# MTAP-Embedded.net
KiCad netlist of a schematic drawn in EAGLE
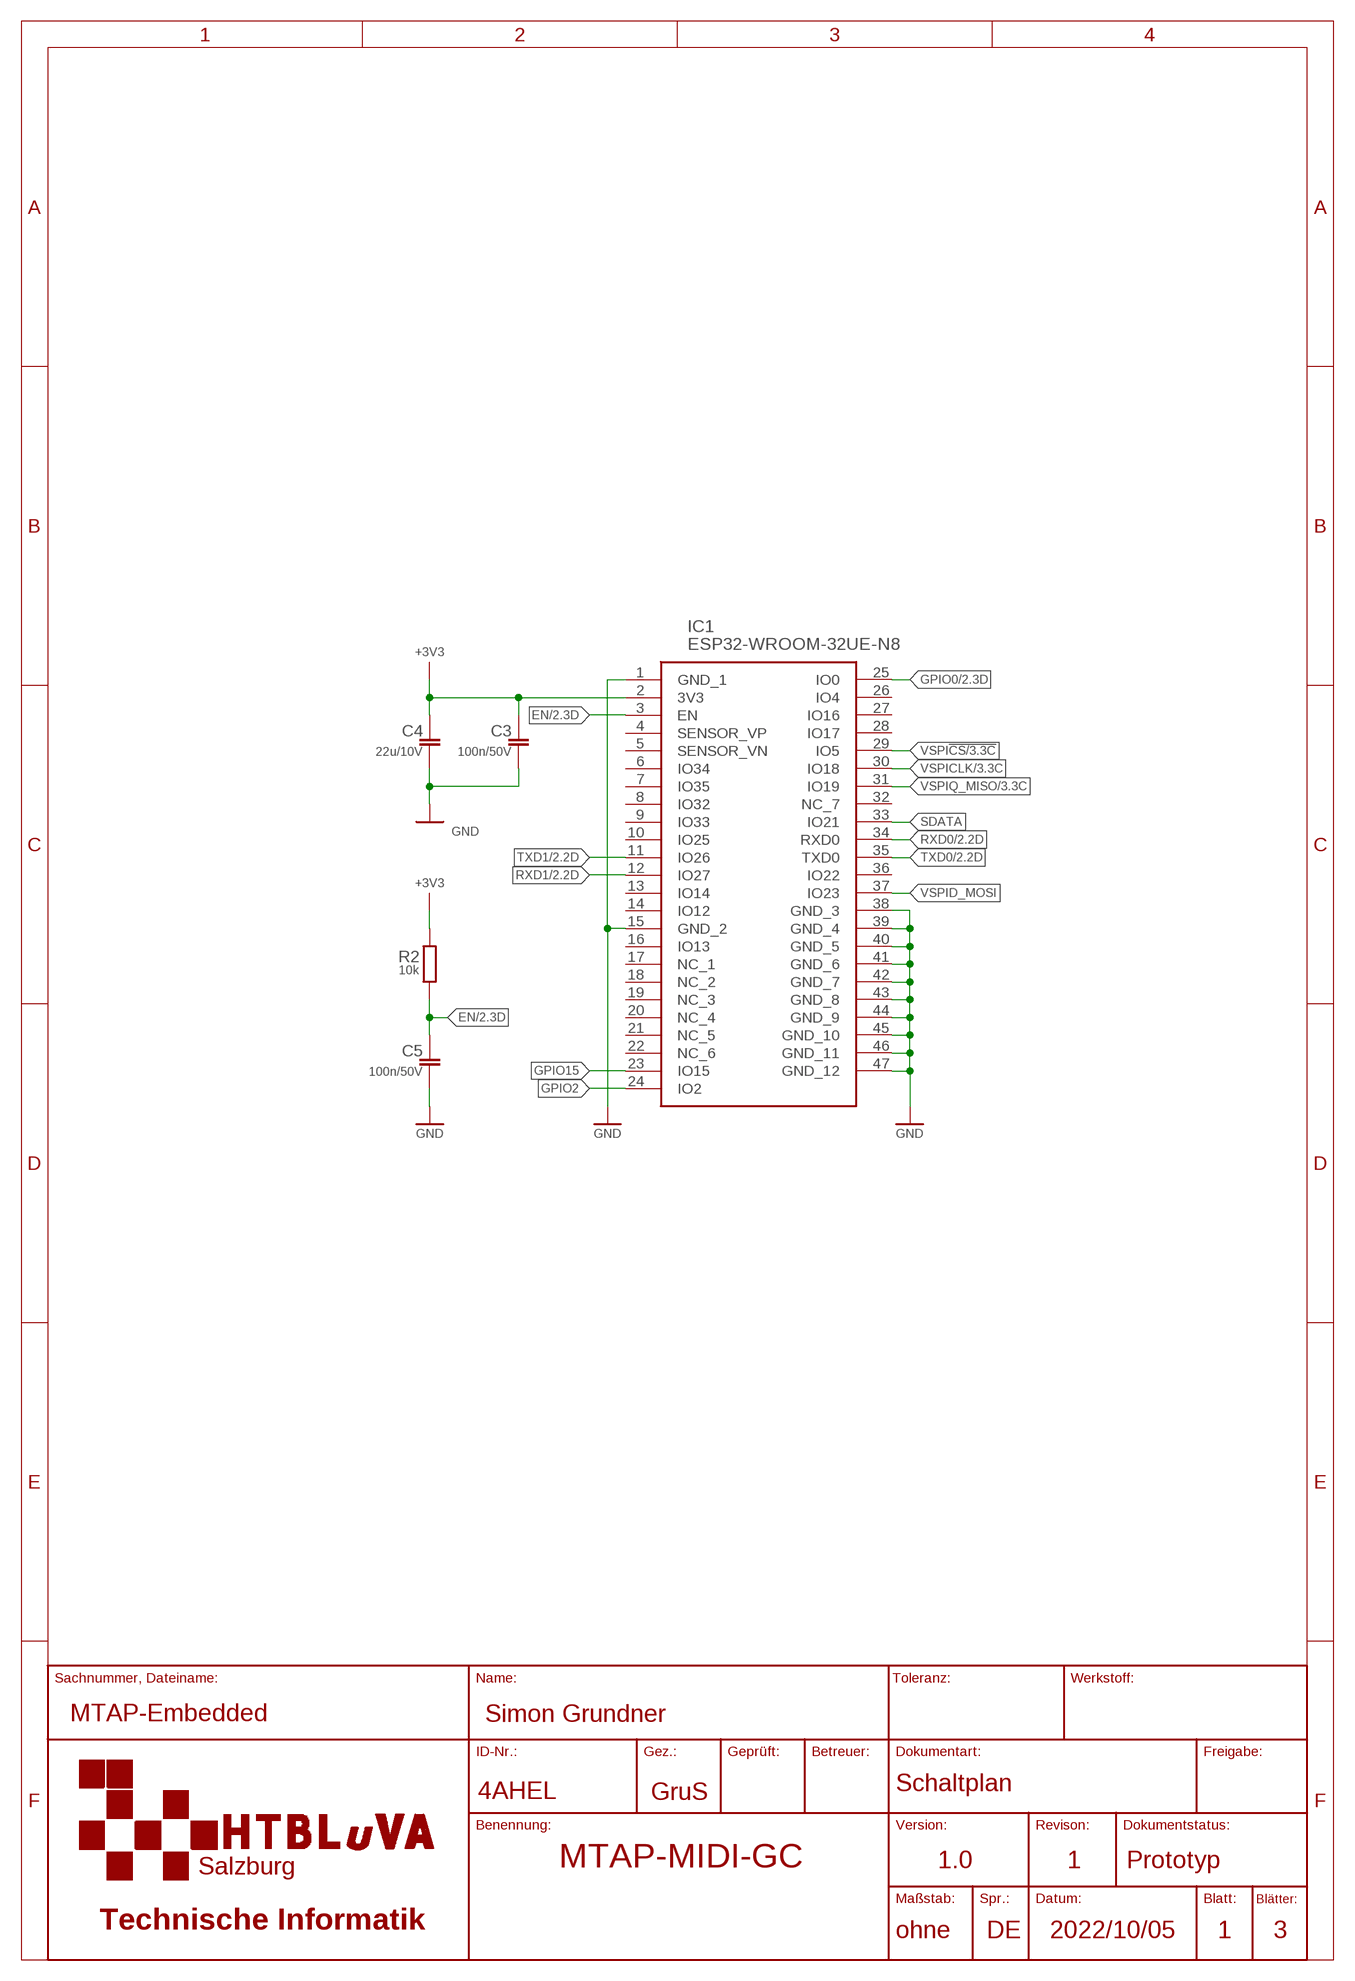
[diagram p0: schematic, sheet 1]
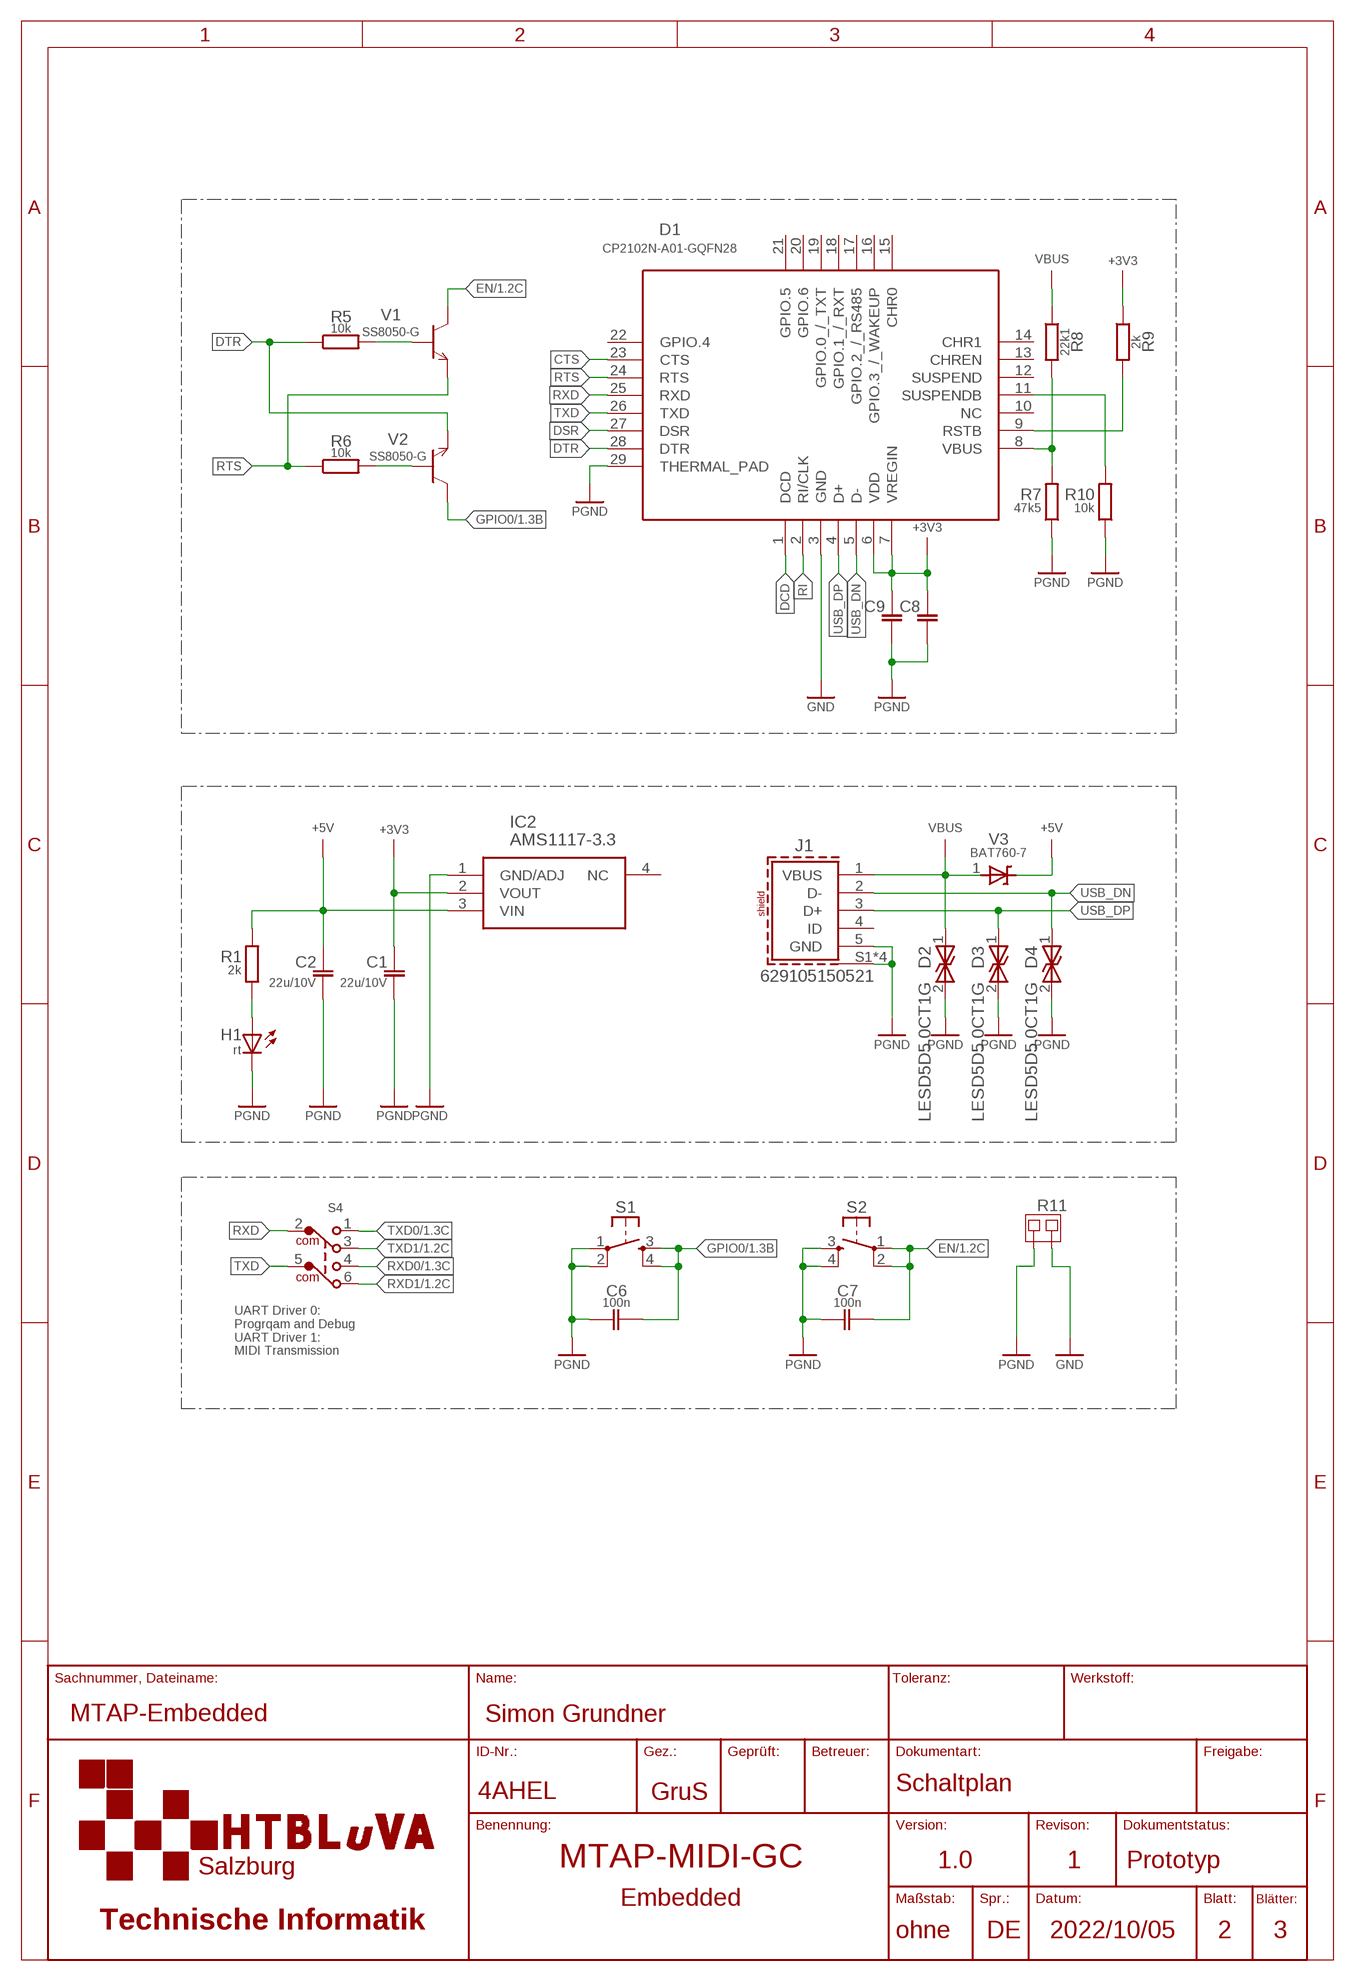
[diagram p1: schematic, sheet 2]
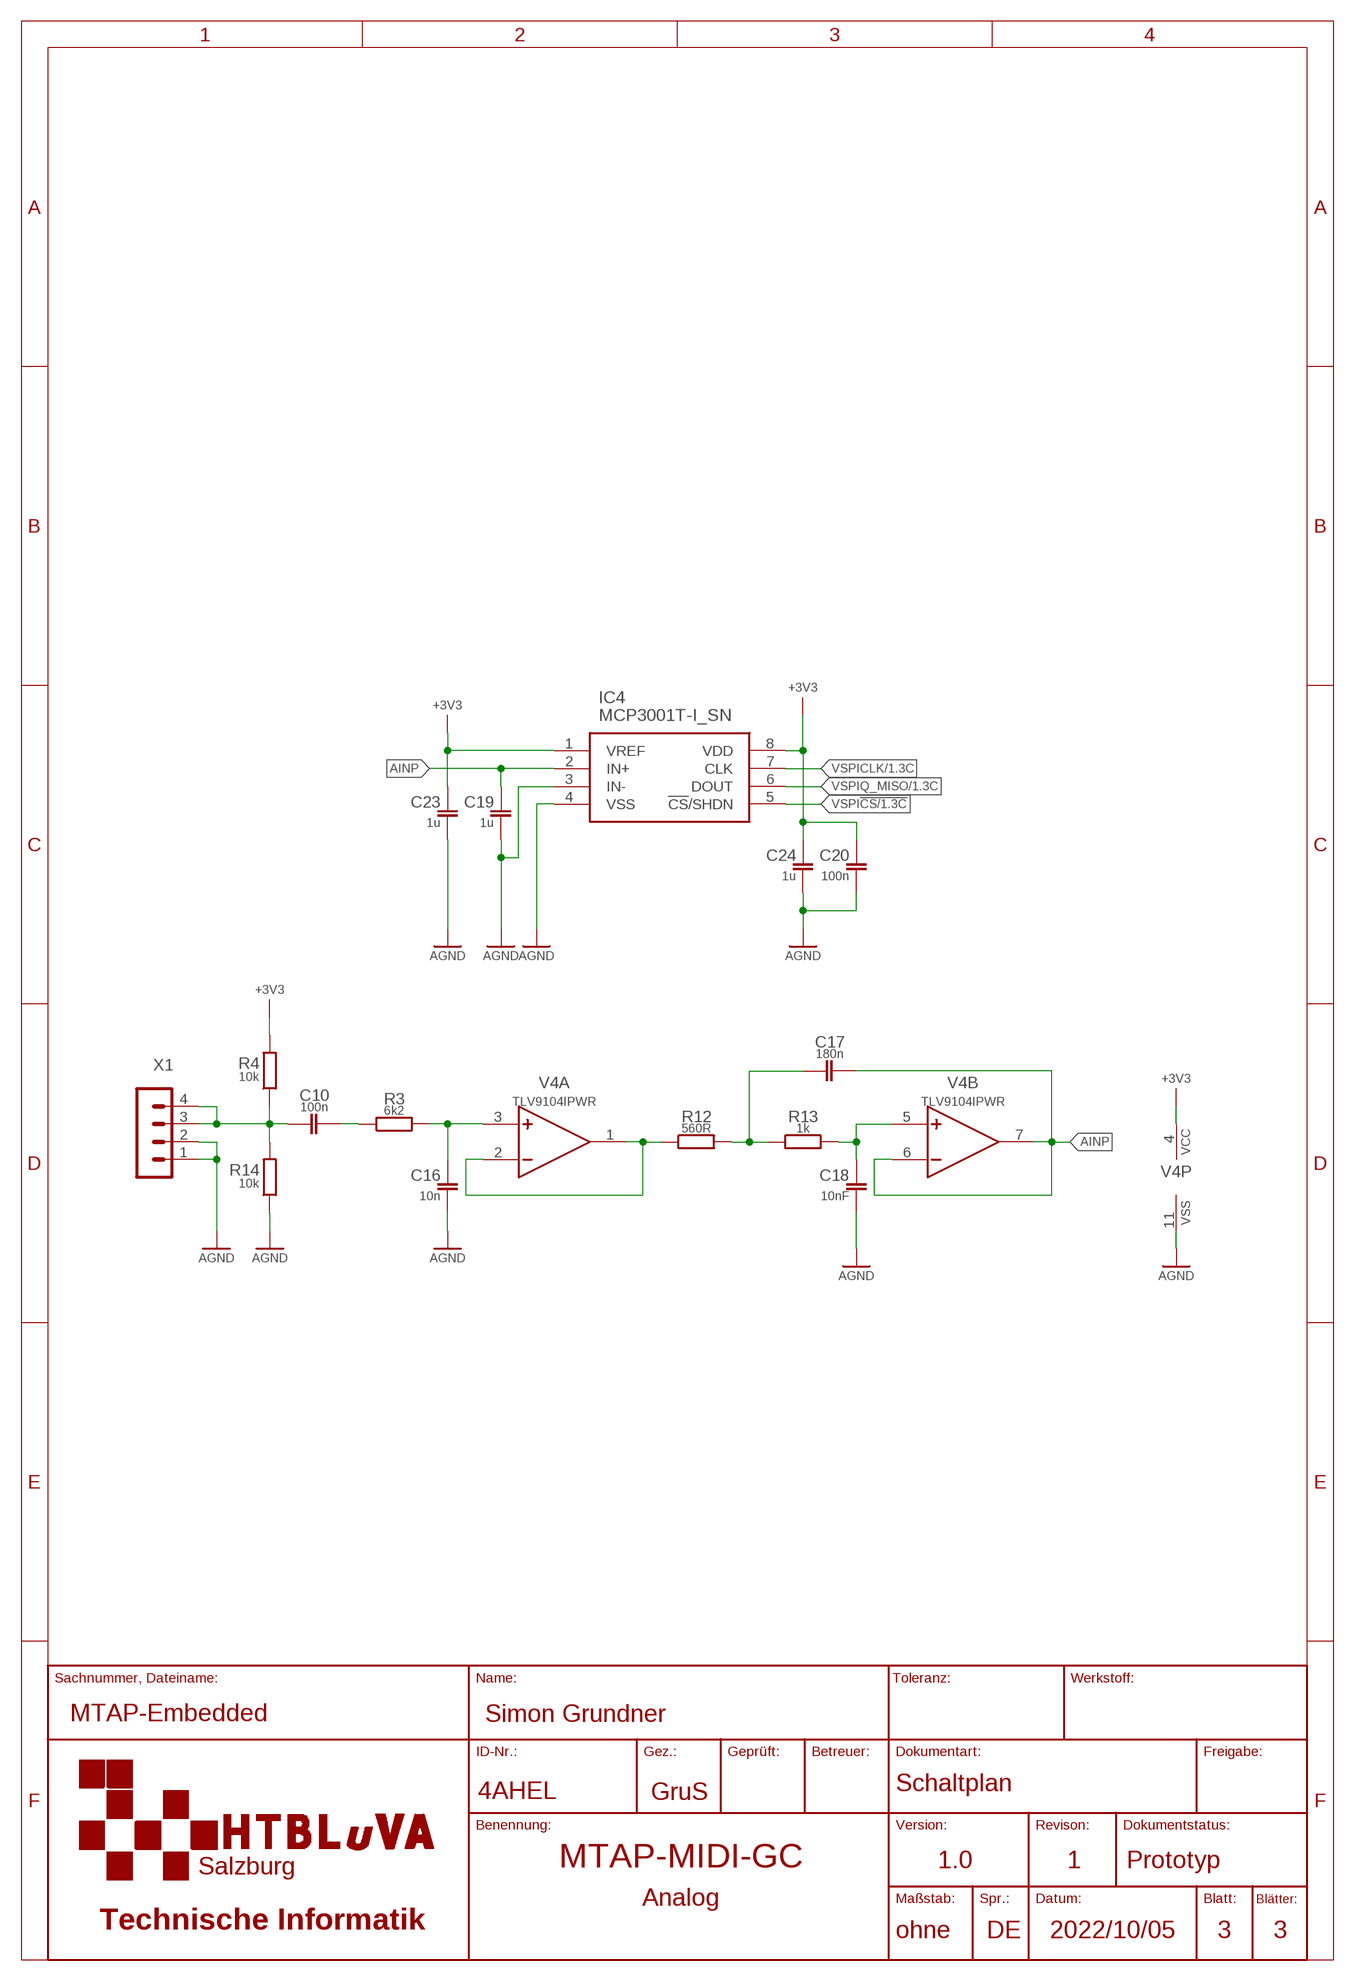
[diagram p2: schematic, sheet 3]

(export (version "E")
  (design (tool "Eeschema 10.0.6"))
  (components
    (comp (ref "C1")
      (value "22u/10V")
      (footprint "eagle-import:C0805")
      (libsource (lib "eagle-import") (part "C-EUC0805"))
    )
    (comp (ref "C2")
      (value "22u/10V")
      (footprint "eagle-import:C0805")
      (libsource (lib "eagle-import") (part "C-EUC0805"))
    )
    (comp (ref "C6")
      (value "100n")
      (footprint "eagle-import:C0805")
      (libsource (lib "eagle-import") (part "C-EULC0805"))
    )
    (comp (ref "C7")
      (value "100n")
      (footprint "eagle-import:C0805")
      (libsource (lib "eagle-import") (part "C-EULC0805"))
    )
    (comp (ref "C8")
      (value "C-EUC0805")
      (footprint "eagle-import:C0805")
      (libsource (lib "eagle-import") (part "C-EUC0805"))
    )
    (comp (ref "C9")
      (value "C-EUC0805")
      (footprint "eagle-import:C0805")
      (libsource (lib "eagle-import") (part "C-EUC0805"))
    )
    (comp (ref "D1")
      (value "CP2102N-A01-GQFN28")
      (footprint "eagle-import:QFN28")
      (fields (field (name "MOUSER_PART_NUMBER") "634-CP2102NA01GQFN28"))
      (libsource (lib "eagle-import") (part "CP2102N-A01-GQFN28"))
    )
    (comp (ref "D2")
      (value "LESD5D5.0CT1G")
      (footprint "eagle-import:SOD523")
      (libsource (lib "eagle-import") (part "LESD5D5.0CT1G"))
    )
    (comp (ref "D3")
      (value "LESD5D5.0CT1G")
      (footprint "eagle-import:SOD523")
      (libsource (lib "eagle-import") (part "LESD5D5.0CT1G"))
    )
    (comp (ref "D4")
      (value "LESD5D5.0CT1G")
      (footprint "eagle-import:SOD523")
      (libsource (lib "eagle-import") (part "LESD5D5.0CT1G"))
    )
    (comp (ref "H1")
      (value "rt")
      (footprint "eagle-import:CHIP-LED0805")
      (libsource (lib "eagle-import") (part "LEDCHIP-LED0805"))
    )
    (comp (ref "IC2")
      (value "AMS1117-3.3")
      (footprint "eagle-import:SOT229P700X180-4N")
      (libsource (lib "eagle-import") (part "AMS1117-3.3"))
    )
    (comp (ref "J1")
      (value "629105150521")
      (footprint "eagle-import:629105150521")
      (libsource (lib "eagle-import") (part "629105150521"))
    )
    (comp (ref "R1")
      (value "2k")
      (footprint "eagle-import:R0805")
      (libsource (lib "eagle-import") (part "R-EUSR0805"))
    )
    (comp (ref "R5")
      (value "10k")
      (footprint "eagle-import:R0805")
      (libsource (lib "eagle-import") (part "R-EU_R0805"))
    )
    (comp (ref "R6")
      (value "10k")
      (footprint "eagle-import:R0805")
      (libsource (lib "eagle-import") (part "R-EU_R0805"))
    )
    (comp (ref "R7")
      (value "47k5")
      (footprint "eagle-import:R0805")
      (libsource (lib "eagle-import") (part "R-EUSR0805"))
    )
    (comp (ref "R8")
      (value "22k1")
      (footprint "eagle-import:R0805")
      (libsource (lib "eagle-import") (part "R-EU_R0805"))
    )
    (comp (ref "R9")
      (value "2k")
      (footprint "eagle-import:R0805")
      (libsource (lib "eagle-import") (part "R-EU_R0805"))
    )
    (comp (ref "R10")
      (value "10k")
      (footprint "eagle-import:R0805")
      (libsource (lib "eagle-import") (part "R-EUSR0805"))
    )
    (comp (ref "R11")
      (value "0R")
      (footprint "eagle-import:MYLIB_SJ-SHORT")
      (libsource (lib "eagle-import") (part "JUMPSMD1FACH-1SHORT"))
    )
    (comp (ref "S1")
      (value "TASTE10XXWE")
      (footprint "eagle-import:WE_436331045822")
      (libsource (lib "eagle-import") (part "TASTE10XXWE"))
    )
    (comp (ref "S2")
      (value "TASTE10XXWE")
      (footprint "eagle-import:WE_436331045822")
      (libsource (lib "eagle-import") (part "TASTE10XXWE"))
    )
    (comp (ref "S4")
      (value "452404020202")
      (footprint "eagle-import:452404020202")
      (libsource (lib "eagle-import") (part "452404020202"))
    )
    (comp (ref "V1")
      (value "SS8050-G")
      (footprint "eagle-import:SOT95P240X115-3N")
      (fields (field (name "MOUSER_PART_NUMBER") "750-SS8050-G"))
      (libsource (lib "eagle-import") (part "SS8050-G"))
    )
    (comp (ref "V2")
      (value "SS8050-G")
      (footprint "eagle-import:SOT95P240X115-3N")
      (fields (field (name "MOUSER_PART_NUMBER") "750-SS8050-G"))
      (libsource (lib "eagle-import") (part "SS8050-G"))
    )
    (comp (ref "V3")
      (value "BAT760-7")
      (footprint "eagle-import:SOD323")
      (fields (field (name "MOUSER_PART_NUMBER") "621-BAT760-7"))
      (libsource (lib "eagle-import") (part "BAT760-7"))
    )
    (comp (ref "C3")
      (value "100n/50V")
      (footprint "eagle-import:C0805")
      (libsource (lib "eagle-import") (part "C-EUC0805"))
    )
    (comp (ref "C4")
      (value "22u/10V")
      (footprint "eagle-import:C0805")
      (libsource (lib "eagle-import") (part "C-EUC0805"))
    )
    (comp (ref "C5")
      (value "100n/50V")
      (footprint "eagle-import:C0805")
      (libsource (lib "eagle-import") (part "C-EUC0805"))
    )
    (comp (ref "IC1")
      (value "ESP32-WROOM-32UE-N8")
      (footprint "eagle-import:ESP32WROOM32UEN8")
      (fields (field (name "MOUSER_PART_NUMBER") "356-ESP32WRM32UE64UH"))
      (libsource (lib "eagle-import") (part "ESP32-WROOM-32UE-N8"))
    )
    (comp (ref "R2")
      (value "10k")
      (footprint "eagle-import:R0805")
      (libsource (lib "eagle-import") (part "R-EUSR0805"))
    )
    (comp (ref "C10")
      (value "100n")
      (footprint "eagle-import:C0805")
      (libsource (lib "eagle-import") (part "C-EULC0805"))
    )
    (comp (ref "C16")
      (value "10n")
      (footprint "eagle-import:C0805")
      (libsource (lib "eagle-import") (part "C-EUC0805"))
    )
    (comp (ref "C17")
      (value "180n")
      (footprint "eagle-import:C0805")
      (libsource (lib "eagle-import") (part "C-EULC0805"))
    )
    (comp (ref "C18")
      (value "10nF")
      (footprint "eagle-import:C0805")
      (libsource (lib "eagle-import") (part "C-EUC0805"))
    )
    (comp (ref "C19")
      (value "1u")
      (footprint "eagle-import:C0805")
      (libsource (lib "eagle-import") (part "C-EUC0805"))
    )
    (comp (ref "C20")
      (value "100n")
      (footprint "eagle-import:C0805")
      (libsource (lib "eagle-import") (part "C-EUC0805"))
    )
    (comp (ref "C23")
      (value "1u")
      (footprint "eagle-import:C0805")
      (libsource (lib "eagle-import") (part "C-EUC0805"))
    )
    (comp (ref "C24")
      (value "1u")
      (footprint "eagle-import:C0805")
      (libsource (lib "eagle-import") (part "C-EUC0805"))
    )
    (comp (ref "IC4")
      (value "MCP3001T-I_SN")
      (footprint "eagle-import:SOIC127P600X175-8N")
      (fields
        (field (name "ARROW_PART_NUMBER") "MCP3001T-I/SN")
        (field (name "MOUSER_PART_NUMBER") "579-MCP3001T-I/SN")
      )
      (libsource (lib "eagle-import") (part "MCP3001T-I_SN"))
    )
    (comp (ref "R3")
      (value "6k2")
      (footprint "eagle-import:R0805")
      (libsource (lib "eagle-import") (part "R-EU_R0805"))
    )
    (comp (ref "R4")
      (value "10k")
      (footprint "eagle-import:R0805")
      (libsource (lib "eagle-import") (part "R-EUSR0805"))
    )
    (comp (ref "R12")
      (value "560R")
      (footprint "eagle-import:R0805")
      (libsource (lib "eagle-import") (part "R-EU_R0805"))
    )
    (comp (ref "R13")
      (value "1k")
      (footprint "eagle-import:R0805")
      (libsource (lib "eagle-import") (part "R-EU_R0805"))
    )
    (comp (ref "R14")
      (value "10k")
      (footprint "eagle-import:R0805")
      (libsource (lib "eagle-import") (part "R-EUSR0805"))
    )
    (comp (ref "V4")
      (value "TLV9104IPWR")
      (footprint "eagle-import:SOP65P640X120-14N")
      (fields (field (name "MOUSER_PART_NUMBER") "595-TLV9104IPWR"))
      (libsource (lib "eagle-import") (part "TLV9104IPWR"))
    )
    (comp (ref "X1")
      (value "MA04-1")
      (footprint "eagle-import:MA04-1")
      (libsource (lib "eagle-import") (part "MA04-1"))
    )
  )
  (nets
    (net (code "1") (name "+3V3") (class "Default")
      (node (ref "C1") (pin "1") (pinfunction "1_1") (pintype "passive"))
      (node (ref "C20") (pin "1") (pinfunction "1_1") (pintype "passive"))
      (node (ref "C23") (pin "1") (pinfunction "1_1") (pintype "passive"))
      (node (ref "C24") (pin "1") (pinfunction "1_1") (pintype "passive"))
      (node (ref "C3") (pin "1") (pinfunction "1_1") (pintype "passive"))
      (node (ref "C4") (pin "1") (pinfunction "1_1") (pintype "passive"))
      (node (ref "C8") (pin "1") (pinfunction "1_1") (pintype "passive"))
      (node (ref "C9") (pin "1") (pinfunction "1_1") (pintype "passive"))
      (node (ref "D1") (pin "6") (pinfunction "VDD_6") (pintype "bidirectional"))
      (node (ref "D1") (pin "7") (pinfunction "VREGIN_7") (pintype "bidirectional"))
      (node (ref "IC1") (pin "2") (pinfunction "3V3_2") (pintype "bidirectional"))
      (node (ref "IC2") (pin "2") (pinfunction "VOUT_2") (pintype "bidirectional"))
      (node (ref "IC4") (pin "1") (pinfunction "VREF_1") (pintype "bidirectional"))
      (node (ref "IC4") (pin "8") (pinfunction "VDD_8") (pintype "bidirectional"))
      (node (ref "R2") (pin "2") (pinfunction "2_2") (pintype "passive"))
      (node (ref "R4") (pin "2") (pinfunction "2_2") (pintype "passive"))
      (node (ref "R9") (pin "1") (pinfunction "1_1") (pintype "passive"))
      (node (ref "V4") (pin "4") (pinfunction "VCC_4") (pintype "power_in"))
    )
    (net (code "2") (name "+5V") (class "Default")
      (node (ref "C2") (pin "1") (pinfunction "1_1") (pintype "passive"))
      (node (ref "IC2") (pin "3") (pinfunction "VIN_3") (pintype "bidirectional"))
      (node (ref "R1") (pin "2") (pinfunction "2_2") (pintype "passive"))
      (node (ref "V3") (pin "2") (pinfunction "A_2") (pintype "output"))
    )
    (net (code "3") (name "AGND") (class "Default")
      (node (ref "C16") (pin "2") (pinfunction "2_2") (pintype "passive"))
      (node (ref "C18") (pin "2") (pinfunction "2_2") (pintype "passive"))
      (node (ref "C19") (pin "2") (pinfunction "2_2") (pintype "passive"))
      (node (ref "C20") (pin "2") (pinfunction "2_2") (pintype "passive"))
      (node (ref "C23") (pin "2") (pinfunction "2_2") (pintype "passive"))
      (node (ref "C24") (pin "2") (pinfunction "2_2") (pintype "passive"))
      (node (ref "IC4") (pin "3") (pinfunction "IN-_3") (pintype "bidirectional"))
      (node (ref "IC4") (pin "4") (pinfunction "VSS_4") (pintype "bidirectional"))
      (node (ref "R14") (pin "1") (pinfunction "1_1") (pintype "passive"))
      (node (ref "V4") (pin "11") (pinfunction "VSS_11") (pintype "power_in"))
      (node (ref "X1") (pin "1") (pinfunction "1_1") (pintype "passive"))
      (node (ref "X1") (pin "2") (pinfunction "2_2") (pintype "passive"))
    )
    (net (code "4") (name "AINP") (class "Default")
      (node (ref "C17") (pin "1") (pinfunction "1_1") (pintype "passive"))
      (node (ref "C19") (pin "1") (pinfunction "1_1") (pintype "passive"))
      (node (ref "IC4") (pin "2") (pinfunction "IN+_2") (pintype "bidirectional"))
      (node (ref "V4") (pin "6") (pinfunction "N_6") (pintype "bidirectional"))
      (node (ref "V4") (pin "7") (pinfunction "O_7") (pintype "bidirectional"))
    )
    (net (code "5") (name "CTS") (class "Default")
      (node (ref "D1") (pin "23") (pinfunction "CTS_23") (pintype "bidirectional"))
    )
    (net (code "6") (name "DCD") (class "Default")
      (node (ref "D1") (pin "1") (pinfunction "DCD_1") (pintype "bidirectional"))
    )
    (net (code "7") (name "DSR") (class "Default")
      (node (ref "D1") (pin "27") (pinfunction "DSR_27") (pintype "bidirectional"))
    )
    (net (code "8") (name "DTR") (class "Default")
      (node (ref "D1") (pin "28") (pinfunction "DTR_28") (pintype "bidirectional"))
      (node (ref "R5") (pin "1") (pinfunction "1_1") (pintype "passive"))
      (node (ref "V2") (pin "2") (pinfunction "E_2") (pintype "passive"))
    )
    (net (code "9") (name "EN") (class "Default")
      (node (ref "C5") (pin "1") (pinfunction "1_1") (pintype "passive"))
      (node (ref "C7") (pin "1") (pinfunction "1_1") (pintype "passive"))
      (node (ref "IC1") (pin "3") (pinfunction "EN_3") (pintype "bidirectional"))
      (node (ref "R2") (pin "1") (pinfunction "1_1") (pintype "passive"))
      (node (ref "S2") (pin "1") (pinfunction "P_1") (pintype "passive"))
      (node (ref "S2") (pin "2") (pinfunction "P1_2") (pintype "passive"))
      (node (ref "V1") (pin "3") (pinfunction "C_3") (pintype "passive"))
    )
    (net (code "10") (name "GND") (class "Default")
      (node (ref "C3") (pin "2") (pinfunction "2_2") (pintype "passive"))
      (node (ref "C4") (pin "2") (pinfunction "2_2") (pintype "passive"))
      (node (ref "C5") (pin "2") (pinfunction "2_2") (pintype "passive"))
      (node (ref "D1") (pin "3") (pinfunction "GND_3") (pintype "bidirectional"))
      (node (ref "IC1") (pin "1") (pinfunction "GND_1_1") (pintype "bidirectional"))
      (node (ref "IC1") (pin "15") (pinfunction "GND_2_15") (pintype "bidirectional"))
      (node (ref "IC1") (pin "38") (pinfunction "GND_3_38") (pintype "bidirectional"))
      (node (ref "IC1") (pin "39") (pinfunction "GND_4_39") (pintype "bidirectional"))
      (node (ref "IC1") (pin "40") (pinfunction "GND_5_40") (pintype "bidirectional"))
      (node (ref "IC1") (pin "41") (pinfunction "GND_6_41") (pintype "bidirectional"))
      (node (ref "IC1") (pin "42") (pinfunction "GND_7_42") (pintype "bidirectional"))
      (node (ref "IC1") (pin "43") (pinfunction "GND_8_43") (pintype "bidirectional"))
      (node (ref "IC1") (pin "44") (pinfunction "GND_9_44") (pintype "bidirectional"))
      (node (ref "IC1") (pin "45") (pinfunction "GND_10_45") (pintype "bidirectional"))
      (node (ref "IC1") (pin "46") (pinfunction "GND_11_46") (pintype "bidirectional"))
      (node (ref "IC1") (pin "47") (pinfunction "GND_12_47") (pintype "bidirectional"))
      (node (ref "R11") (pin "2") (pinfunction "2_2") (pintype "passive"))
    )
    (net (code "11") (name "GPIO0") (class "Default")
      (node (ref "C6") (pin "1") (pinfunction "1_1") (pintype "passive"))
      (node (ref "IC1") (pin "25") (pinfunction "IO0_25") (pintype "bidirectional"))
      (node (ref "S1") (pin "3") (pinfunction "S_3") (pintype "passive"))
      (node (ref "S1") (pin "4") (pinfunction "S1_4") (pintype "passive"))
      (node (ref "V2") (pin "3") (pinfunction "C_3") (pintype "passive"))
    )
    (net (code "12") (name "GPIO2") (class "Default")
      (node (ref "IC1") (pin "24") (pinfunction "IO2_24") (pintype "bidirectional"))
    )
    (net (code "13") (name "GPIO15") (class "Default")
      (node (ref "IC1") (pin "23") (pinfunction "IO15_23") (pintype "bidirectional"))
    )
    (net (code "14") (name "Net-(C10-Pad1)") (class "Default")
      (node (ref "C10") (pin "1") (pinfunction "1_1") (pintype "passive"))
      (node (ref "R3") (pin "1") (pinfunction "1_1") (pintype "passive"))
    )
    (net (code "15") (name "Net-(C10-Pad2)") (class "Default")
      (node (ref "C10") (pin "2") (pinfunction "2_2") (pintype "passive"))
      (node (ref "R14") (pin "2") (pinfunction "2_2") (pintype "passive"))
      (node (ref "R4") (pin "1") (pinfunction "1_1") (pintype "passive"))
      (node (ref "X1") (pin "3") (pinfunction "3_3") (pintype "passive"))
      (node (ref "X1") (pin "4") (pinfunction "4_4") (pintype "passive"))
    )
    (net (code "16") (name "Net-(C17-Pad2)") (class "Default")
      (node (ref "C17") (pin "2") (pinfunction "2_2") (pintype "passive"))
      (node (ref "R12") (pin "2") (pinfunction "2_2") (pintype "passive"))
      (node (ref "R13") (pin "1") (pinfunction "1_1") (pintype "passive"))
    )
    (net (code "17") (name "Net-(D1-RSTB)") (class "Default")
      (node (ref "D1") (pin "9") (pinfunction "RSTB_9") (pintype "bidirectional"))
      (node (ref "R9") (pin "2") (pinfunction "2_2") (pintype "passive"))
    )
    (net (code "18") (name "Net-(D1-SUSPENDB)") (class "Default")
      (node (ref "D1") (pin "11") (pinfunction "SUSPENDB_11") (pintype "bidirectional"))
      (node (ref "R10") (pin "2") (pinfunction "2_2") (pintype "passive"))
    )
    (net (code "19") (name "Net-(D1-VBUS)") (class "Default")
      (node (ref "D1") (pin "8") (pinfunction "VBUS_8") (pintype "bidirectional"))
      (node (ref "R7") (pin "2") (pinfunction "2_2") (pintype "passive"))
      (node (ref "R8") (pin "2") (pinfunction "2_2") (pintype "passive"))
    )
    (net (code "20") (name "Net-(H1-PadA)") (class "Default")
      (node (ref "H1") (pin "A") (pinfunction "A_A") (pintype "passive"))
      (node (ref "R1") (pin "1") (pinfunction "1_1") (pintype "passive"))
    )
    (net (code "21") (name "Net-(V1-B)") (class "Default")
      (node (ref "R5") (pin "2") (pinfunction "2_2") (pintype "passive"))
      (node (ref "V1") (pin "1") (pinfunction "B_1") (pintype "passive"))
    )
    (net (code "22") (name "Net-(V2-B)") (class "Default")
      (node (ref "R6") (pin "2") (pinfunction "2_2") (pintype "passive"))
      (node (ref "V2") (pin "1") (pinfunction "B_1") (pintype "passive"))
    )
    (net (code "23") (name "Net-(V4A-N)") (class "Default")
      (node (ref "R12") (pin "1") (pinfunction "1_1") (pintype "passive"))
      (node (ref "V4") (pin "1") (pinfunction "O_1") (pintype "bidirectional"))
      (node (ref "V4") (pin "2") (pinfunction "N_2") (pintype "bidirectional"))
    )
    (net (code "24") (name "Net-(V4A-P)") (class "Default")
      (node (ref "C16") (pin "1") (pinfunction "1_1") (pintype "passive"))
      (node (ref "R3") (pin "2") (pinfunction "2_2") (pintype "passive"))
      (node (ref "V4") (pin "3") (pinfunction "P_3") (pintype "bidirectional"))
    )
    (net (code "25") (name "Net-(V4B-P)") (class "Default")
      (node (ref "C18") (pin "1") (pinfunction "1_1") (pintype "passive"))
      (node (ref "R13") (pin "2") (pinfunction "2_2") (pintype "passive"))
      (node (ref "V4") (pin "5") (pinfunction "P_5") (pintype "bidirectional"))
    )
    (net (code "26") (name "PGND") (class "Default")
      (node (ref "C1") (pin "2") (pinfunction "2_2") (pintype "passive"))
      (node (ref "C2") (pin "2") (pinfunction "2_2") (pintype "passive"))
      (node (ref "C6") (pin "2") (pinfunction "2_2") (pintype "passive"))
      (node (ref "C7") (pin "2") (pinfunction "2_2") (pintype "passive"))
      (node (ref "C8") (pin "2") (pinfunction "2_2") (pintype "passive"))
      (node (ref "C9") (pin "2") (pinfunction "2_2") (pintype "passive"))
      (node (ref "D1") (pin "29") (pinfunction "THERMAL_PAD_29") (pintype "bidirectional"))
      (node (ref "D2") (pin "2") (pinfunction "2_2") (pintype "bidirectional"))
      (node (ref "D3") (pin "2") (pinfunction "2_2") (pintype "bidirectional"))
      (node (ref "D4") (pin "2") (pinfunction "2_2") (pintype "bidirectional"))
      (node (ref "H1") (pin "C") (pinfunction "C_C") (pintype "passive"))
      (node (ref "IC2") (pin "1") (pinfunction "GND/ADJ_1") (pintype "bidirectional"))
      (node (ref "J1") (pin "5") (pinfunction "GND_5") (pintype "passive"))
      (node (ref "J1") (pin "S1") (pinfunction "SHIELD_S1") (pintype "passive"))
      (node (ref "J1") (pin "S2") (pinfunction "SHIELD_S2") (pintype "passive"))
      (node (ref "J1") (pin "S3") (pinfunction "SHIELD_S3") (pintype "passive"))
      (node (ref "J1") (pin "S4") (pinfunction "SHIELD_S4") (pintype "passive"))
      (node (ref "R10") (pin "1") (pinfunction "1_1") (pintype "passive"))
      (node (ref "R11") (pin "1") (pinfunction "1_1") (pintype "passive"))
      (node (ref "R7") (pin "1") (pinfunction "1_1") (pintype "passive"))
      (node (ref "S1") (pin "1") (pinfunction "P_1") (pintype "passive"))
      (node (ref "S1") (pin "2") (pinfunction "P1_2") (pintype "passive"))
      (node (ref "S2") (pin "3") (pinfunction "S_3") (pintype "passive"))
      (node (ref "S2") (pin "4") (pinfunction "S1_4") (pintype "passive"))
    )
    (net (code "27") (name "RI") (class "Default")
      (node (ref "D1") (pin "2") (pinfunction "RI/CLK_2") (pintype "bidirectional"))
    )
    (net (code "28") (name "RTS") (class "Default")
      (node (ref "D1") (pin "24") (pinfunction "RTS_24") (pintype "bidirectional"))
      (node (ref "R6") (pin "1") (pinfunction "1_1") (pintype "passive"))
      (node (ref "V1") (pin "2") (pinfunction "E_2") (pintype "passive"))
    )
    (net (code "29") (name "RXD") (class "Default")
      (node (ref "D1") (pin "25") (pinfunction "RXD_25") (pintype "bidirectional"))
      (node (ref "S4") (pin "2") (pinfunction "COM_2") (pintype "passive"))
    )
    (net (code "30") (name "RXD0") (class "Default")
      (node (ref "IC1") (pin "34") (pinfunction "RXD0_34") (pintype "bidirectional"))
      (node (ref "S4") (pin "4") (pinfunction "4_4") (pintype "passive"))
    )
    (net (code "31") (name "RXD1") (class "Default")
      (node (ref "IC1") (pin "12") (pinfunction "IO27_12") (pintype "bidirectional"))
      (node (ref "S4") (pin "6") (pinfunction "6_6") (pintype "passive"))
    )
    (net (code "32") (name "SDATA") (class "Default")
      (node (ref "IC1") (pin "33") (pinfunction "IO21_33") (pintype "bidirectional"))
    )
    (net (code "33") (name "TXD") (class "Default")
      (node (ref "D1") (pin "26") (pinfunction "TXD_26") (pintype "bidirectional"))
      (node (ref "S4") (pin "5") (pinfunction "COM1_5") (pintype "passive"))
    )
    (net (code "34") (name "TXD0") (class "Default")
      (node (ref "IC1") (pin "35") (pinfunction "TXD0_35") (pintype "bidirectional"))
      (node (ref "S4") (pin "1") (pinfunction "1_1") (pintype "passive"))
    )
    (net (code "35") (name "TXD1") (class "Default")
      (node (ref "IC1") (pin "11") (pinfunction "IO26_11") (pintype "bidirectional"))
      (node (ref "S4") (pin "3") (pinfunction "3_3") (pintype "passive"))
    )
    (net (code "36") (name "USB_DN") (class "Default")
      (node (ref "D1") (pin "5") (pinfunction "D-_5") (pintype "bidirectional"))
      (node (ref "D4") (pin "1") (pinfunction "1_1") (pintype "bidirectional"))
      (node (ref "J1") (pin "2") (pinfunction "D-_2") (pintype "passive"))
    )
    (net (code "37") (name "USB_DP") (class "Default")
      (node (ref "D1") (pin "4") (pinfunction "D+_4") (pintype "bidirectional"))
      (node (ref "D3") (pin "1") (pinfunction "1_1") (pintype "bidirectional"))
      (node (ref "J1") (pin "3") (pinfunction "D+_3") (pintype "passive"))
    )
    (net (code "38") (name "VBUS") (class "Default")
      (node (ref "D2") (pin "1") (pinfunction "1_1") (pintype "bidirectional"))
      (node (ref "J1") (pin "1") (pinfunction "VBUS_1") (pintype "passive"))
      (node (ref "R8") (pin "1") (pinfunction "1_1") (pintype "passive"))
      (node (ref "V3") (pin "1") (pinfunction "K_1") (pintype "input"))
    )
    (net (code "39") (name "VSPICLK") (class "Default")
      (node (ref "IC1") (pin "30") (pinfunction "IO18_30") (pintype "bidirectional"))
      (node (ref "IC4") (pin "7") (pinfunction "CLK_7") (pintype "bidirectional"))
    )
    (net (code "40") (name "VSPID_MOSI") (class "Default")
      (node (ref "IC1") (pin "37") (pinfunction "IO23_37") (pintype "bidirectional"))
    )
    (net (code "41") (name "VSPIQ_MISO") (class "Default")
      (node (ref "IC1") (pin "31") (pinfunction "IO19_31") (pintype "bidirectional"))
      (node (ref "IC4") (pin "6") (pinfunction "DOUT_6") (pintype "bidirectional"))
    )
    (net (code "42") (name "VSPI~{CS}") (class "Default")
      (node (ref "IC1") (pin "29") (pinfunction "IO5_29") (pintype "bidirectional"))
      (node (ref "IC4") (pin "5") (pinfunction "~{CS}/SHDN_5") (pintype "bidirectional"))
    )
    (net (code "43") (name "unconnected-(D1-CHR0-Pad15)") (class "Default")
      (node (ref "D1") (pin "15") (pinfunction "CHR0_15") (pintype "bidirectional"))
    )
    (net (code "44") (name "unconnected-(D1-CHR1-Pad14)") (class "Default")
      (node (ref "D1") (pin "14") (pinfunction "CHR1_14") (pintype "bidirectional"))
    )
    (net (code "45") (name "unconnected-(D1-CHREN-Pad13)") (class "Default")
      (node (ref "D1") (pin "13") (pinfunction "CHREN_13") (pintype "bidirectional"))
    )
    (net (code "46") (name "unconnected-(D1-GPIO.0_{slash}_TXT-Pad19)") (class "Default")
      (node (ref "D1") (pin "19") (pinfunction "GPIO.0_/_TXT_19") (pintype "bidirectional"))
    )
    (net (code "47") (name "unconnected-(D1-GPIO.1_{slash}_RXT-Pad18)") (class "Default")
      (node (ref "D1") (pin "18") (pinfunction "GPIO.1_/_RXT_18") (pintype "bidirectional"))
    )
    (net (code "48") (name "unconnected-(D1-GPIO.2_{slash}_RS485-Pad17)") (class "Default")
      (node (ref "D1") (pin "17") (pinfunction "GPIO.2_/_RS485_17") (pintype "bidirectional"))
    )
    (net (code "49") (name "unconnected-(D1-GPIO.3_{slash}_WAKEUP-Pad16)") (class "Default")
      (node (ref "D1") (pin "16") (pinfunction "GPIO.3_/_WAKEUP_16") (pintype "bidirectional"))
    )
    (net (code "50") (name "unconnected-(D1-GPIO.4-Pad22)") (class "Default")
      (node (ref "D1") (pin "22") (pinfunction "GPIO.4_22") (pintype "bidirectional"))
    )
    (net (code "51") (name "unconnected-(D1-GPIO.5-Pad21)") (class "Default")
      (node (ref "D1") (pin "21") (pinfunction "GPIO.5_21") (pintype "bidirectional"))
    )
    (net (code "52") (name "unconnected-(D1-GPIO.6-Pad20)") (class "Default")
      (node (ref "D1") (pin "20") (pinfunction "GPIO.6_20") (pintype "bidirectional"))
    )
    (net (code "53") (name "unconnected-(D1-NC-Pad10)") (class "Default")
      (node (ref "D1") (pin "10") (pinfunction "NC_10") (pintype "no_connect"))
    )
    (net (code "54") (name "unconnected-(D1-SUSPEND-Pad12)") (class "Default")
      (node (ref "D1") (pin "12") (pinfunction "SUSPEND_12") (pintype "bidirectional"))
    )
    (net (code "55") (name "unconnected-(IC1-IO4-Pad26)") (class "Default")
      (node (ref "IC1") (pin "26") (pinfunction "IO4_26") (pintype "bidirectional"))
    )
    (net (code "56") (name "unconnected-(IC1-IO12-Pad14)") (class "Default")
      (node (ref "IC1") (pin "14") (pinfunction "IO12_14") (pintype "bidirectional"))
    )
    (net (code "57") (name "unconnected-(IC1-IO13-Pad16)") (class "Default")
      (node (ref "IC1") (pin "16") (pinfunction "IO13_16") (pintype "bidirectional"))
    )
    (net (code "58") (name "unconnected-(IC1-IO14-Pad13)") (class "Default")
      (node (ref "IC1") (pin "13") (pinfunction "IO14_13") (pintype "bidirectional"))
    )
    (net (code "59") (name "unconnected-(IC1-IO16-Pad27)") (class "Default")
      (node (ref "IC1") (pin "27") (pinfunction "IO16_27") (pintype "bidirectional"))
    )
    (net (code "60") (name "unconnected-(IC1-IO17-Pad28)") (class "Default")
      (node (ref "IC1") (pin "28") (pinfunction "IO17_28") (pintype "bidirectional"))
    )
    (net (code "61") (name "unconnected-(IC1-IO22-Pad36)") (class "Default")
      (node (ref "IC1") (pin "36") (pinfunction "IO22_36") (pintype "bidirectional"))
    )
    (net (code "62") (name "unconnected-(IC1-IO25-Pad10)") (class "Default")
      (node (ref "IC1") (pin "10") (pinfunction "IO25_10") (pintype "bidirectional"))
    )
    (net (code "63") (name "unconnected-(IC1-IO32-Pad8)") (class "Default")
      (node (ref "IC1") (pin "8") (pinfunction "IO32_8") (pintype "bidirectional"))
    )
    (net (code "64") (name "unconnected-(IC1-IO33-Pad9)") (class "Default")
      (node (ref "IC1") (pin "9") (pinfunction "IO33_9") (pintype "bidirectional"))
    )
    (net (code "65") (name "unconnected-(IC1-IO34-Pad6)") (class "Default")
      (node (ref "IC1") (pin "6") (pinfunction "IO34_6") (pintype "bidirectional"))
    )
    (net (code "66") (name "unconnected-(IC1-IO35-Pad7)") (class "Default")
      (node (ref "IC1") (pin "7") (pinfunction "IO35_7") (pintype "bidirectional"))
    )
    (net (code "67") (name "unconnected-(IC1-NC_1-Pad17)") (class "Default")
      (node (ref "IC1") (pin "17") (pinfunction "NC_1_17") (pintype "bidirectional"))
    )
    (net (code "68") (name "unconnected-(IC1-NC_2-Pad18)") (class "Default")
      (node (ref "IC1") (pin "18") (pinfunction "NC_2_18") (pintype "bidirectional"))
    )
    (net (code "69") (name "unconnected-(IC1-NC_3-Pad19)") (class "Default")
      (node (ref "IC1") (pin "19") (pinfunction "NC_3_19") (pintype "bidirectional"))
    )
    (net (code "70") (name "unconnected-(IC1-NC_4-Pad20)") (class "Default")
      (node (ref "IC1") (pin "20") (pinfunction "NC_4_20") (pintype "bidirectional"))
    )
    (net (code "71") (name "unconnected-(IC1-NC_5-Pad21)") (class "Default")
      (node (ref "IC1") (pin "21") (pinfunction "NC_5_21") (pintype "bidirectional"))
    )
    (net (code "72") (name "unconnected-(IC1-NC_6-Pad22)") (class "Default")
      (node (ref "IC1") (pin "22") (pinfunction "NC_6_22") (pintype "bidirectional"))
    )
    (net (code "73") (name "unconnected-(IC1-NC_7-Pad32)") (class "Default")
      (node (ref "IC1") (pin "32") (pinfunction "NC_7_32") (pintype "bidirectional"))
    )
    (net (code "74") (name "unconnected-(IC1-SENSOR_VN-Pad5)") (class "Default")
      (node (ref "IC1") (pin "5") (pinfunction "SENSOR_VN_5") (pintype "bidirectional"))
    )
    (net (code "75") (name "unconnected-(IC1-SENSOR_VP-Pad4)") (class "Default")
      (node (ref "IC1") (pin "4") (pinfunction "SENSOR_VP_4") (pintype "bidirectional"))
    )
    (net (code "76") (name "unconnected-(IC2-NC-Pad4)") (class "Default")
      (node (ref "IC2") (pin "4") (pinfunction "NC_4") (pintype "no_connect"))
    )
    (net (code "77") (name "unconnected-(J1-ID-Pad4)") (class "Default")
      (node (ref "J1") (pin "4") (pinfunction "ID_4") (pintype "passive"))
    )
  )
)
